# SI7051.net
KiCad netlist of a schematic drawn in Altium Designer
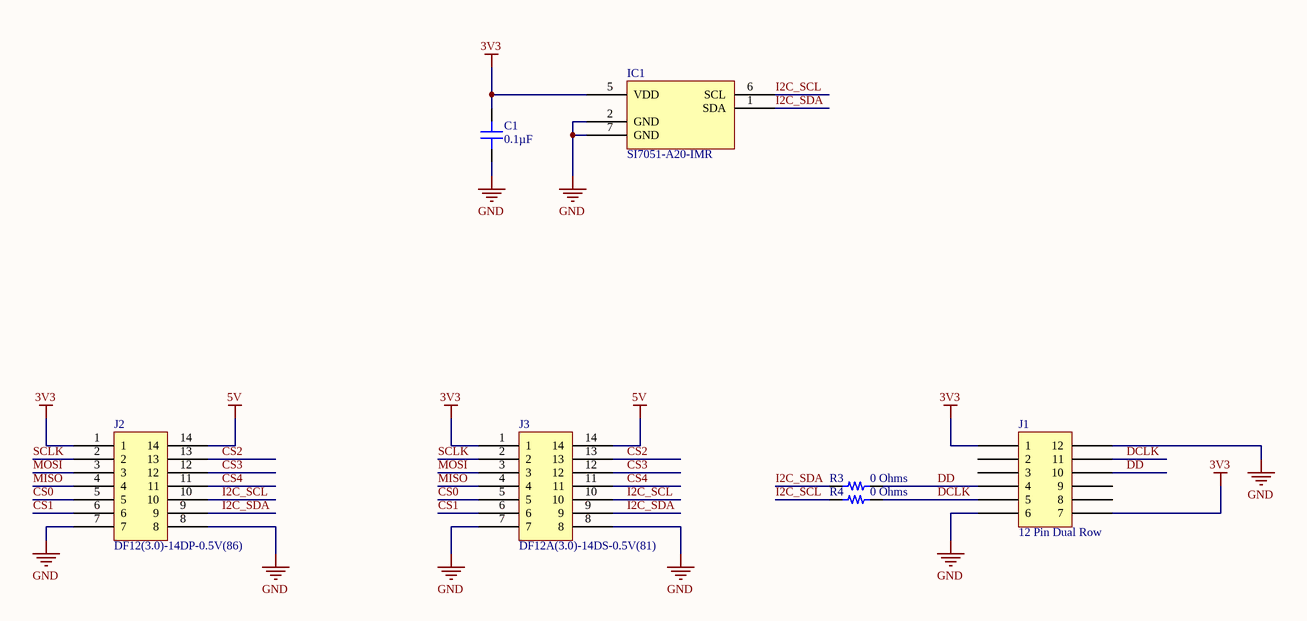
[diagram p0: SI7051.SchDoc]

(export (version "E")
  (design (tool "Eeschema 10.0.6"))
  (components
    (comp (ref "C1")
      (value "0.1µF")
      (footprint "CAP 0603_1608")
      (description "CAP CER 0.1UF 16V Y5V 0603")
      (fields (field (name "PART NUMBER") "CC0603ZRY5V7BB104") (field (name "MANUFACTURER") "Yageo"))
      (libsource (lib "altiumlibrary.com") (part "Capacitor"))
    )
    (comp (ref "IC1")
      (value "SI7051-A20-IMR")
      (footprint "SILICON LABS DFN-6 3x3MM")
      (description "SENSOR DIGITAL -40C-125C 6DFN")
      (fields (field (name "MANUFACTURER") "Silicon Labs"))
      (libsource (lib "altiumlibrary.com") (part "Silicon Labs SI7051-A20"))
    )
    (comp (ref "J1")
      (value "12 Pin Dual Row")
      (footprint "TE 5650118-3 Card Edge")
      (libsource (lib "CelestialUseful") (part "12 Pin Dual Row"))
    )
    (comp (ref "J2")
      (value "DF12(3.0)-14DP-0.5V(86)")
      (footprint "HIROSE DF12 3.0-14DP-0.5V 86")
      (description "CONN HDR 14POS SMD GOLD")
      (fields (field (name "MANUFACTURER") "Hirose Electric Co Ltd"))
      (libsource (lib "altiumlibrary.com") (part "14 Pin Dual Row"))
    )
    (comp (ref "J3")
      (value "DF12A(3.0)-14DS-0.5V(81)")
      (footprint "HIROSE DF12A 3.0-14DS-0.5V 81")
      (description "CONN RCPT 14POS SMD GOLD")
      (fields (field (name "MANUFACTURER") "Hirose Electric Co Ltd"))
      (libsource (lib "altiumlibrary.com") (part "14 Pin Dual Row"))
    )
    (comp (ref "R3")
      (value "0 Ohms")
      (footprint "RES 0603_1608")
      (description "RES SMD 0 OHM JUMPER 1/10W 0603")
      (fields
        (field (name "PART NUMBER") "ERJ-3GEY0R00V")
        (field (name "MANUFACTURER") "Panasonic Electronic Components")
      )
      (libsource (lib "altiumlibrary.com") (part "Resistor"))
    )
    (comp (ref "R4")
      (value "0 Ohms")
      (footprint "RES 0603_1608")
      (description "RES SMD 0 OHM JUMPER 1/10W 0603")
      (fields
        (field (name "PART NUMBER") "ERJ-3GEY0R00V")
        (field (name "MANUFACTURER") "Panasonic Electronic Components")
      )
      (libsource (lib "altiumlibrary.com") (part "Resistor"))
    )
  )
  (nets
    (net (code "1") (name "/CS0") (class "Default")
      (node (ref "J2") (pin "5") (pinfunction "5_5") (pintype "passive"))
      (node (ref "J3") (pin "5") (pinfunction "5_5") (pintype "passive"))
    )
    (net (code "2") (name "/CS1") (class "Default")
      (node (ref "J2") (pin "6") (pinfunction "6_6") (pintype "passive"))
      (node (ref "J3") (pin "6") (pinfunction "6_6") (pintype "passive"))
    )
    (net (code "3") (name "/CS2") (class "Default")
      (node (ref "J2") (pin "13") (pinfunction "13_13") (pintype "passive"))
      (node (ref "J3") (pin "13") (pinfunction "13_13") (pintype "passive"))
    )
    (net (code "4") (name "/CS3") (class "Default")
      (node (ref "J2") (pin "12") (pinfunction "12_12") (pintype "passive"))
      (node (ref "J3") (pin "12") (pinfunction "12_12") (pintype "passive"))
    )
    (net (code "5") (name "/CS4") (class "Default")
      (node (ref "J2") (pin "11") (pinfunction "11_11") (pintype "passive"))
      (node (ref "J3") (pin "11") (pinfunction "11_11") (pintype "passive"))
    )
    (net (code "6") (name "/DCLK") (class "Default")
      (node (ref "J1") (pin "11") (pinfunction "11_11") (pintype "passive"))
      (node (ref "J1") (pin "5") (pinfunction "5_5") (pintype "passive"))
      (node (ref "R4") (pin "2") (pinfunction "2_2") (pintype "passive"))
    )
    (net (code "7") (name "/DD") (class "Default")
      (node (ref "J1") (pin "10") (pinfunction "10_10") (pintype "passive"))
      (node (ref "J1") (pin "4") (pinfunction "4_4") (pintype "passive"))
      (node (ref "R3") (pin "2") (pinfunction "2_2") (pintype "passive"))
    )
    (net (code "8") (name "/I2C_SCL") (class "Default")
      (node (ref "IC1") (pin "6") (pinfunction "SCL_6") (pintype "passive"))
      (node (ref "J2") (pin "10") (pinfunction "10_10") (pintype "passive"))
      (node (ref "J3") (pin "10") (pinfunction "10_10") (pintype "passive"))
      (node (ref "R4") (pin "1") (pinfunction "1_1") (pintype "passive"))
    )
    (net (code "9") (name "/I2C_SDA") (class "Default")
      (node (ref "IC1") (pin "1") (pinfunction "SDA_1") (pintype "passive"))
      (node (ref "J2") (pin "9") (pinfunction "9_9") (pintype "passive"))
      (node (ref "J3") (pin "9") (pinfunction "9_9") (pintype "passive"))
      (node (ref "R3") (pin "1") (pinfunction "1_1") (pintype "passive"))
    )
    (net (code "10") (name "/MISO") (class "Default")
      (node (ref "J2") (pin "4") (pinfunction "4_4") (pintype "passive"))
      (node (ref "J3") (pin "4") (pinfunction "4_4") (pintype "passive"))
    )
    (net (code "11") (name "/MOSI") (class "Default")
      (node (ref "J2") (pin "3") (pinfunction "3_3") (pintype "passive"))
      (node (ref "J3") (pin "3") (pinfunction "3_3") (pintype "passive"))
    )
    (net (code "12") (name "/SCLK") (class "Default")
      (node (ref "J2") (pin "2") (pinfunction "2_2") (pintype "passive"))
      (node (ref "J3") (pin "2") (pinfunction "2_2") (pintype "passive"))
    )
    (net (code "13") (name "3V3") (class "Default")
      (node (ref "C1") (pin "1") (pinfunction "1_1") (pintype "passive"))
      (node (ref "IC1") (pin "5") (pinfunction "VDD_5") (pintype "passive"))
      (node (ref "J1") (pin "1") (pinfunction "1_1") (pintype "passive"))
      (node (ref "J1") (pin "7") (pinfunction "7_7") (pintype "passive"))
      (node (ref "J2") (pin "1") (pinfunction "1_1") (pintype "passive"))
      (node (ref "J3") (pin "1") (pinfunction "1_1") (pintype "passive"))
    )
    (net (code "14") (name "5V") (class "Default")
      (node (ref "J2") (pin "14") (pinfunction "14_14") (pintype "passive"))
      (node (ref "J3") (pin "14") (pinfunction "14_14") (pintype "passive"))
    )
    (net (code "15") (name "GND") (class "Default")
      (node (ref "C1") (pin "2") (pinfunction "2_2") (pintype "passive"))
      (node (ref "IC1") (pin "2") (pinfunction "GND_2") (pintype "passive"))
      (node (ref "IC1") (pin "7") (pinfunction "GND_7") (pintype "passive"))
      (node (ref "J1") (pin "12") (pinfunction "12_12") (pintype "passive"))
      (node (ref "J1") (pin "6") (pinfunction "6_6") (pintype "passive"))
      (node (ref "J2") (pin "7") (pinfunction "7_7") (pintype "passive"))
      (node (ref "J2") (pin "8") (pinfunction "8_8") (pintype "passive"))
      (node (ref "J3") (pin "7") (pinfunction "7_7") (pintype "passive"))
      (node (ref "J3") (pin "8") (pinfunction "8_8") (pintype "passive"))
    )
    (net (code "16") (name "unconnected-(J1-Pad2)") (class "Default")
      (node (ref "J1") (pin "2") (pinfunction "2_2") (pintype "passive"))
    )
    (net (code "17") (name "unconnected-(J1-Pad3)") (class "Default")
      (node (ref "J1") (pin "3") (pinfunction "3_3") (pintype "passive"))
    )
    (net (code "18") (name "unconnected-(J1-Pad8)") (class "Default")
      (node (ref "J1") (pin "8") (pinfunction "8_8") (pintype "passive"))
    )
    (net (code "19") (name "unconnected-(J1-Pad9)") (class "Default")
      (node (ref "J1") (pin "9") (pinfunction "9_9") (pintype "passive"))
    )
  )
)
